# Sheet1.net
KiCad netlist of a schematic drawn in Altium Designer
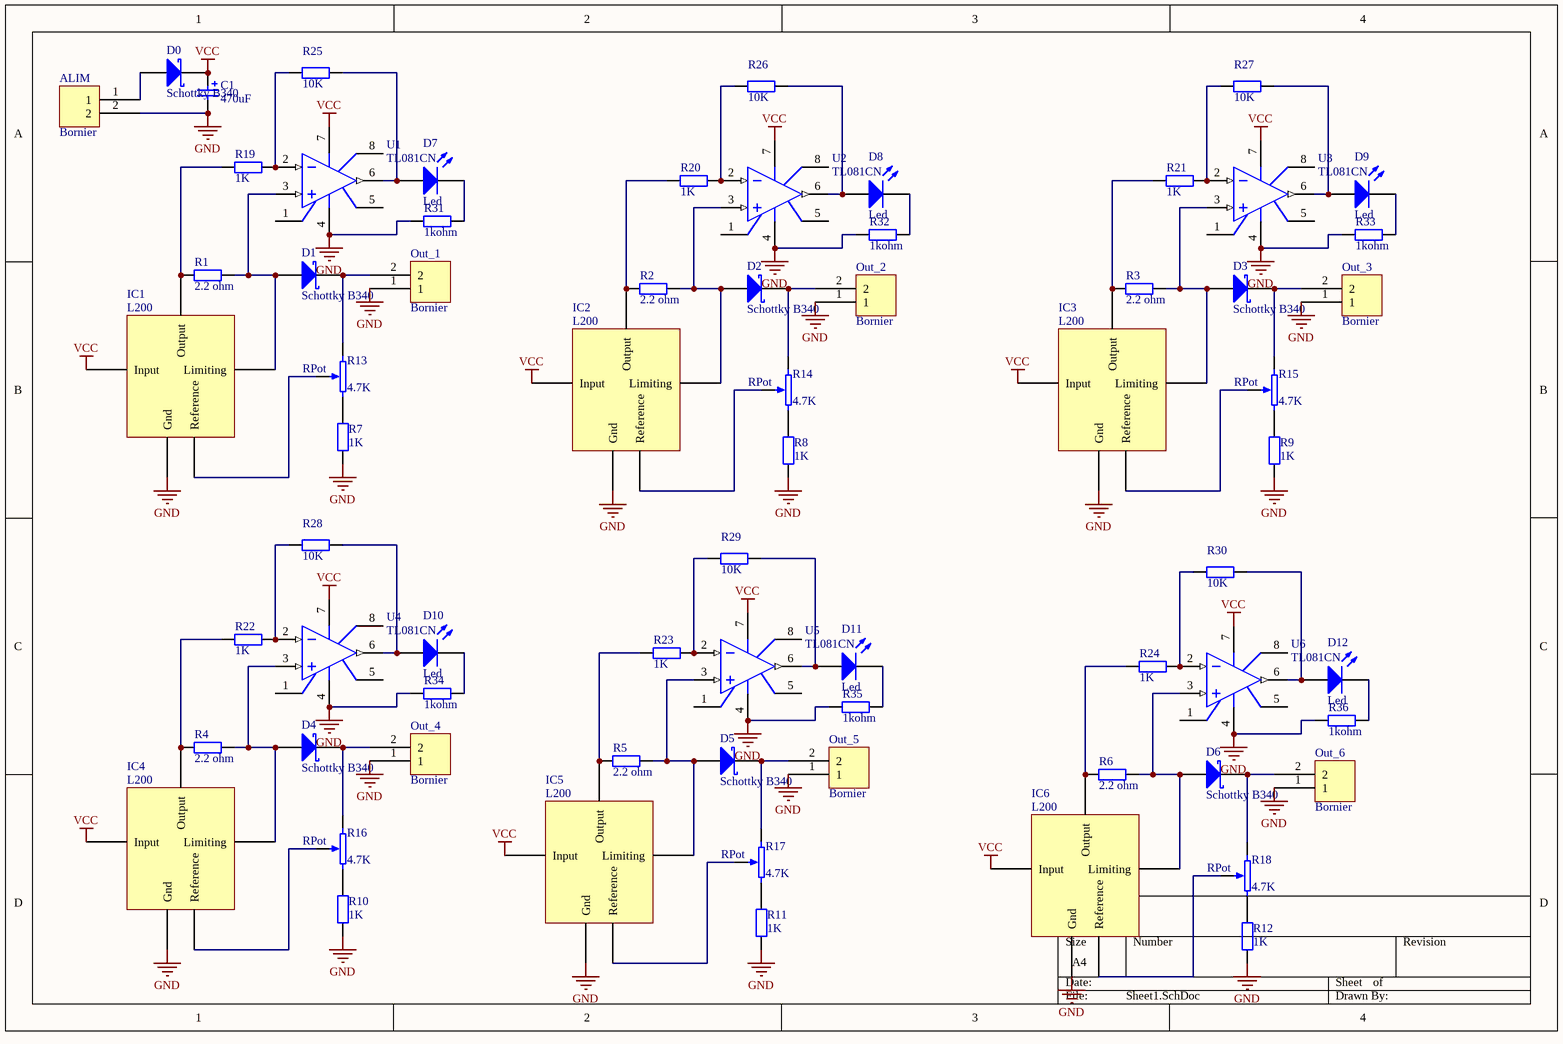
[diagram p0: Sheet1.SchDoc]

(export (version "E")
  (design (tool "Eeschema 10.0.6"))
  (components
    (comp (ref "ALIM") (value "Bornier") (footprint "Bornier") (libsource (lib "") (part "Bornier2_1")))
    (comp (ref "C1")
      (value "470uF")
      (footprint "Capa_pol1")
      (libsource (lib "lib_Robotronik") (part "Capa Pol"))
    )
    (comp (ref "D0")
      (value "Schottky B340")
      (footprint "SMC")
      (libsource (lib "lib_Robotronik") (part "Schottky B340"))
    )
    (comp (ref "D1")
      (value "Schottky B340")
      (footprint "SMC")
      (libsource (lib "lib_Robotronik") (part "Schottky B340"))
    )
    (comp (ref "D2")
      (value "Schottky B340")
      (footprint "SMC")
      (libsource (lib "lib_Robotronik") (part "Schottky B340"))
    )
    (comp (ref "D3")
      (value "Schottky B340")
      (footprint "SMC")
      (libsource (lib "lib_Robotronik") (part "Schottky B340"))
    )
    (comp (ref "D4")
      (value "Schottky B340")
      (footprint "SMC")
      (libsource (lib "lib_Robotronik") (part "Schottky B340"))
    )
    (comp (ref "D5")
      (value "Schottky B340")
      (footprint "SMC")
      (libsource (lib "lib_Robotronik") (part "Schottky B340"))
    )
    (comp (ref "D6")
      (value "Schottky B340")
      (footprint "SMC")
      (libsource (lib "lib_Robotronik") (part "Schottky B340"))
    )
    (comp (ref "D7")
      (value "Led")
      (footprint "LED")
      (description "LED")
      (fields (field (name "PUBLISHER") "Altium Limited"))
      (libsource (lib "LIBRAIRIE_INTEGREE_PHELMA1") (part "Led"))
    )
    (comp (ref "D8")
      (value "Led")
      (footprint "LED")
      (description "LED")
      (fields (field (name "PUBLISHER") "Altium Limited"))
      (libsource (lib "LIBRAIRIE_INTEGREE_PHELMA1") (part "Led"))
    )
    (comp (ref "D9")
      (value "Led")
      (footprint "LED")
      (description "LED")
      (fields (field (name "PUBLISHER") "Altium Limited"))
      (libsource (lib "LIBRAIRIE_INTEGREE_PHELMA1") (part "Led"))
    )
    (comp (ref "D10")
      (value "Led")
      (footprint "LED")
      (description "LED")
      (fields (field (name "PUBLISHER") "Altium Limited"))
      (libsource (lib "LIBRAIRIE_INTEGREE_PHELMA1") (part "Led"))
    )
    (comp (ref "D11")
      (value "Led")
      (footprint "LED")
      (description "LED")
      (fields (field (name "PUBLISHER") "Altium Limited"))
      (libsource (lib "LIBRAIRIE_INTEGREE_PHELMA1") (part "Led"))
    )
    (comp (ref "D12")
      (value "Led")
      (footprint "LED")
      (description "LED")
      (fields (field (name "PUBLISHER") "Altium Limited"))
      (libsource (lib "LIBRAIRIE_INTEGREE_PHELMA1") (part "Led"))
    )
    (comp (ref "IC1") (value "L200") (footprint "Pentawatt") (libsource (lib "lib_Robotronik") (part "L200")))
    (comp (ref "IC2") (value "L200") (footprint "Pentawatt") (libsource (lib "lib_Robotronik") (part "L200")))
    (comp (ref "IC3") (value "L200") (footprint "Pentawatt") (libsource (lib "lib_Robotronik") (part "L200")))
    (comp (ref "IC4") (value "L200") (footprint "Pentawatt") (libsource (lib "lib_Robotronik") (part "L200")))
    (comp (ref "IC5") (value "L200") (footprint "Pentawatt") (libsource (lib "lib_Robotronik") (part "L200")))
    (comp (ref "IC6") (value "L200") (footprint "Pentawatt") (libsource (lib "lib_Robotronik") (part "L200")))
    (comp (ref "Out_1")
      (value "Bornier")
      (footprint "Bornier")
      (libsource (lib "lib_Robotronik") (part "Bornier2"))
    )
    (comp (ref "Out_2")
      (value "Bornier")
      (footprint "Bornier")
      (libsource (lib "lib_Robotronik") (part "Bornier2"))
    )
    (comp (ref "Out_3")
      (value "Bornier")
      (footprint "Bornier")
      (libsource (lib "lib_Robotronik") (part "Bornier2"))
    )
    (comp (ref "Out_4")
      (value "Bornier")
      (footprint "Bornier")
      (libsource (lib "lib_Robotronik") (part "Bornier2"))
    )
    (comp (ref "Out_5")
      (value "Bornier")
      (footprint "Bornier")
      (libsource (lib "lib_Robotronik") (part "Bornier2"))
    )
    (comp (ref "Out_6")
      (value "Bornier")
      (footprint "Bornier")
      (libsource (lib "lib_Robotronik") (part "Bornier2"))
    )
    (comp (ref "R1")
      (value "2.2 ohm")
      (footprint "traversant 1/4W")
      (libsource (lib "") (part "Resistance_2"))
    )
    (comp (ref "R2")
      (value "2.2 ohm")
      (footprint "traversant 1/4W")
      (libsource (lib "") (part "Resistance_2"))
    )
    (comp (ref "R3")
      (value "2.2 ohm")
      (footprint "traversant 1/4W")
      (libsource (lib "") (part "Resistance_2"))
    )
    (comp (ref "R4")
      (value "2.2 ohm")
      (footprint "traversant 1/4W")
      (libsource (lib "") (part "Resistance_2"))
    )
    (comp (ref "R5")
      (value "2.2 ohm")
      (footprint "traversant 1/4W")
      (libsource (lib "") (part "Resistance_2"))
    )
    (comp (ref "R6")
      (value "2.2 ohm")
      (footprint "traversant 1/4W")
      (libsource (lib "") (part "Resistance_2"))
    )
    (comp (ref "R7") (value "1K") (footprint "traversant 1/4W") (libsource (lib "") (part "Resistance_1")))
    (comp (ref "R8") (value "1K") (footprint "traversant 1/4W") (libsource (lib "") (part "Resistance_1")))
    (comp (ref "R9") (value "1K") (footprint "traversant 1/4W") (libsource (lib "") (part "Resistance_1")))
    (comp (ref "R10") (value "1K") (footprint "traversant 1/4W") (libsource (lib "") (part "Resistance_1")))
    (comp (ref "R11") (value "1K") (footprint "traversant 1/4W") (libsource (lib "") (part "Resistance_1")))
    (comp (ref "R12") (value "1K") (footprint "traversant 1/4W") (libsource (lib "") (part "Resistance_1")))
    (comp (ref "R13")
      (value "RPot")
      (footprint "AJUSTABLE")
      (description "Potentiometer")
      (fields (field (name "ALTIUM_VALUE") "4.7K") (field (name "PUBLISHER") "Altium Limited"))
      (libsource (lib "LIBRAIRIE_INTEGREE_PHELMA1") (part "RPot"))
    )
    (comp (ref "R14")
      (value "RPot")
      (footprint "AJUSTABLE")
      (description "Potentiometer")
      (fields (field (name "ALTIUM_VALUE") "4.7K") (field (name "PUBLISHER") "Altium Limited"))
      (libsource (lib "LIBRAIRIE_INTEGREE_PHELMA1") (part "RPot"))
    )
    (comp (ref "R15")
      (value "RPot")
      (footprint "AJUSTABLE")
      (description "Potentiometer")
      (fields (field (name "ALTIUM_VALUE") "4.7K") (field (name "PUBLISHER") "Altium Limited"))
      (libsource (lib "LIBRAIRIE_INTEGREE_PHELMA1") (part "RPot"))
    )
    (comp (ref "R16")
      (value "RPot")
      (footprint "AJUSTABLE")
      (description "Potentiometer")
      (fields (field (name "ALTIUM_VALUE") "4.7K") (field (name "PUBLISHER") "Altium Limited"))
      (libsource (lib "LIBRAIRIE_INTEGREE_PHELMA1") (part "RPot"))
    )
    (comp (ref "R17")
      (value "RPot")
      (footprint "AJUSTABLE")
      (description "Potentiometer")
      (fields (field (name "ALTIUM_VALUE") "4.7K") (field (name "PUBLISHER") "Altium Limited"))
      (libsource (lib "LIBRAIRIE_INTEGREE_PHELMA1") (part "RPot"))
    )
    (comp (ref "R18")
      (value "RPot")
      (footprint "AJUSTABLE")
      (description "Potentiometer")
      (fields (field (name "ALTIUM_VALUE") "4.7K") (field (name "PUBLISHER") "Altium Limited"))
      (libsource (lib "LIBRAIRIE_INTEGREE_PHELMA1") (part "RPot"))
    )
    (comp (ref "R19") (value "1K") (footprint "traversant 1/4W") (libsource (lib "") (part "Resistance_2")))
    (comp (ref "R20") (value "1K") (footprint "traversant 1/4W") (libsource (lib "") (part "Resistance_2")))
    (comp (ref "R21") (value "1K") (footprint "traversant 1/4W") (libsource (lib "") (part "Resistance_2")))
    (comp (ref "R22") (value "1K") (footprint "traversant 1/4W") (libsource (lib "") (part "Resistance_2")))
    (comp (ref "R23") (value "1K") (footprint "traversant 1/4W") (libsource (lib "") (part "Resistance_2")))
    (comp (ref "R24") (value "1K") (footprint "traversant 1/4W") (libsource (lib "") (part "Resistance_2")))
    (comp (ref "R25") (value "10K") (footprint "traversant 1/4W") (libsource (lib "") (part "Resistance_2")))
    (comp (ref "R26") (value "10K") (footprint "traversant 1/4W") (libsource (lib "") (part "Resistance_2")))
    (comp (ref "R27") (value "10K") (footprint "traversant 1/4W") (libsource (lib "") (part "Resistance_2")))
    (comp (ref "R28") (value "10K") (footprint "traversant 1/4W") (libsource (lib "") (part "Resistance_2")))
    (comp (ref "R29") (value "10K") (footprint "traversant 1/4W") (libsource (lib "") (part "Resistance_2")))
    (comp (ref "R30") (value "10K") (footprint "traversant 1/4W") (libsource (lib "") (part "Resistance_2")))
    (comp (ref "R31")
      (value "1kohm")
      (footprint "traversant 1/4W")
      (libsource (lib "lib_Robotronik") (part "Resistance"))
    )
    (comp (ref "R32")
      (value "1kohm")
      (footprint "traversant 1/4W")
      (libsource (lib "lib_Robotronik") (part "Resistance"))
    )
    (comp (ref "R33")
      (value "1kohm")
      (footprint "traversant 1/4W")
      (libsource (lib "lib_Robotronik") (part "Resistance"))
    )
    (comp (ref "R34")
      (value "1kohm")
      (footprint "traversant 1/4W")
      (libsource (lib "lib_Robotronik") (part "Resistance"))
    )
    (comp (ref "R35")
      (value "1kohm")
      (footprint "traversant 1/4W")
      (libsource (lib "lib_Robotronik") (part "Resistance"))
    )
    (comp (ref "R36")
      (value "1kohm")
      (footprint "traversant 1/4W")
      (libsource (lib "lib_Robotronik") (part "Resistance"))
    )
    (comp (ref "U1")
      (value "TL081CN")
      (footprint "DIP8")
      (description "General-Purpose J-FET Single Operational Amplifier")
      (fields (field (name "PUBLISHER") "Altium Limited"))
      (libsource (lib "LIBRAIRIE_INTEGREE_PHELMA1") (part "TL081CN"))
    )
    (comp (ref "U2")
      (value "TL081CN")
      (footprint "DIP8")
      (description "General-Purpose J-FET Single Operational Amplifier")
      (fields (field (name "PUBLISHER") "Altium Limited"))
      (libsource (lib "LIBRAIRIE_INTEGREE_PHELMA1") (part "TL081CN"))
    )
    (comp (ref "U3")
      (value "TL081CN")
      (footprint "DIP8")
      (description "General-Purpose J-FET Single Operational Amplifier")
      (fields (field (name "PUBLISHER") "Altium Limited"))
      (libsource (lib "LIBRAIRIE_INTEGREE_PHELMA1") (part "TL081CN"))
    )
    (comp (ref "U4")
      (value "TL081CN")
      (footprint "DIP8")
      (description "General-Purpose J-FET Single Operational Amplifier")
      (fields (field (name "PUBLISHER") "Altium Limited"))
      (libsource (lib "LIBRAIRIE_INTEGREE_PHELMA1") (part "TL081CN"))
    )
    (comp (ref "U5")
      (value "TL081CN")
      (footprint "DIP8")
      (description "General-Purpose J-FET Single Operational Amplifier")
      (fields (field (name "PUBLISHER") "Altium Limited"))
      (libsource (lib "LIBRAIRIE_INTEGREE_PHELMA1") (part "TL081CN"))
    )
    (comp (ref "U6")
      (value "TL081CN")
      (footprint "DIP8")
      (description "General-Purpose J-FET Single Operational Amplifier")
      (fields (field (name "PUBLISHER") "Altium Limited"))
      (libsource (lib "LIBRAIRIE_INTEGREE_PHELMA1") (part "TL081CN"))
    )
  )
  (nets
    (net (code "1") (name "GND") (class "Default")
      (node (ref "ALIM") (pin "2") (pinfunction "2_2") (pintype "passive"))
      (node (ref "C1") (pin "2") (pinfunction "2_2") (pintype "passive"))
      (node (ref "IC1") (pin "3") (pinfunction "Gnd_3") (pintype "passive"))
      (node (ref "IC2") (pin "3") (pinfunction "Gnd_3") (pintype "passive"))
      (node (ref "IC3") (pin "3") (pinfunction "Gnd_3") (pintype "passive"))
      (node (ref "IC4") (pin "3") (pinfunction "Gnd_3") (pintype "passive"))
      (node (ref "IC5") (pin "3") (pinfunction "Gnd_3") (pintype "passive"))
      (node (ref "IC6") (pin "3") (pinfunction "Gnd_3") (pintype "passive"))
      (node (ref "Out_1") (pin "1") (pinfunction "1_1") (pintype "passive"))
      (node (ref "Out_2") (pin "1") (pinfunction "1_1") (pintype "passive"))
      (node (ref "Out_3") (pin "1") (pinfunction "1_1") (pintype "passive"))
      (node (ref "Out_4") (pin "1") (pinfunction "1_1") (pintype "passive"))
      (node (ref "Out_5") (pin "1") (pinfunction "1_1") (pintype "passive"))
      (node (ref "Out_6") (pin "1") (pinfunction "1_1") (pintype "passive"))
      (node (ref "R10") (pin "1") (pinfunction "1_1") (pintype "passive"))
      (node (ref "R11") (pin "1") (pinfunction "1_1") (pintype "passive"))
      (node (ref "R12") (pin "1") (pinfunction "1_1") (pintype "passive"))
      (node (ref "R31") (pin "1") (pinfunction "1_1") (pintype "passive"))
      (node (ref "R32") (pin "1") (pinfunction "1_1") (pintype "passive"))
      (node (ref "R33") (pin "1") (pinfunction "1_1") (pintype "passive"))
      (node (ref "R34") (pin "1") (pinfunction "1_1") (pintype "passive"))
      (node (ref "R35") (pin "1") (pinfunction "1_1") (pintype "passive"))
      (node (ref "R36") (pin "1") (pinfunction "1_1") (pintype "passive"))
      (node (ref "R7") (pin "1") (pinfunction "1_1") (pintype "passive"))
      (node (ref "R8") (pin "1") (pinfunction "1_1") (pintype "passive"))
      (node (ref "R9") (pin "1") (pinfunction "1_1") (pintype "passive"))
      (node (ref "U1") (pin "4") (pinfunction "V-_4") (pintype "power_in"))
      (node (ref "U2") (pin "4") (pinfunction "V-_4") (pintype "power_in"))
      (node (ref "U3") (pin "4") (pinfunction "V-_4") (pintype "power_in"))
      (node (ref "U4") (pin "4") (pinfunction "V-_4") (pintype "power_in"))
      (node (ref "U5") (pin "4") (pinfunction "V-_4") (pintype "power_in"))
      (node (ref "U6") (pin "4") (pinfunction "V-_4") (pintype "power_in"))
    )
    (net (code "2") (name "Net-(D0-A)") (class "Default")
      (node (ref "ALIM") (pin "1") (pinfunction "1_1") (pintype "passive"))
      (node (ref "D0") (pin "1") (pinfunction "A_1") (pintype "passive"))
    )
    (net (code "3") (name "Net-(D1-A)") (class "Default")
      (node (ref "D1") (pin "1") (pinfunction "A_1") (pintype "passive"))
      (node (ref "IC1") (pin "2") (pinfunction "Limiting_2") (pintype "passive"))
      (node (ref "R1") (pin "1") (pinfunction "1_1") (pintype "passive"))
      (node (ref "U1") (pin "3") (pinfunction "IN+_3") (pintype "input"))
    )
    (net (code "4") (name "Net-(D1-K)") (class "Default")
      (node (ref "D1") (pin "2") (pinfunction "K_2") (pintype "passive"))
      (node (ref "Out_1") (pin "2") (pinfunction "2_2") (pintype "passive"))
      (node (ref "R13") (pin "3") (pinfunction "TOP_3") (pintype "passive"))
    )
    (net (code "5") (name "Net-(D2-A)") (class "Default")
      (node (ref "D2") (pin "1") (pinfunction "A_1") (pintype "passive"))
      (node (ref "IC2") (pin "2") (pinfunction "Limiting_2") (pintype "passive"))
      (node (ref "R2") (pin "1") (pinfunction "1_1") (pintype "passive"))
      (node (ref "U2") (pin "3") (pinfunction "IN+_3") (pintype "input"))
    )
    (net (code "6") (name "Net-(D2-K)") (class "Default")
      (node (ref "D2") (pin "2") (pinfunction "K_2") (pintype "passive"))
      (node (ref "Out_2") (pin "2") (pinfunction "2_2") (pintype "passive"))
      (node (ref "R14") (pin "3") (pinfunction "TOP_3") (pintype "passive"))
    )
    (net (code "7") (name "Net-(D3-A)") (class "Default")
      (node (ref "D3") (pin "1") (pinfunction "A_1") (pintype "passive"))
      (node (ref "IC3") (pin "2") (pinfunction "Limiting_2") (pintype "passive"))
      (node (ref "R3") (pin "1") (pinfunction "1_1") (pintype "passive"))
      (node (ref "U3") (pin "3") (pinfunction "IN+_3") (pintype "input"))
    )
    (net (code "8") (name "Net-(D3-K)") (class "Default")
      (node (ref "D3") (pin "2") (pinfunction "K_2") (pintype "passive"))
      (node (ref "Out_3") (pin "2") (pinfunction "2_2") (pintype "passive"))
      (node (ref "R15") (pin "3") (pinfunction "TOP_3") (pintype "passive"))
    )
    (net (code "9") (name "Net-(D4-A)") (class "Default")
      (node (ref "D4") (pin "1") (pinfunction "A_1") (pintype "passive"))
      (node (ref "IC4") (pin "2") (pinfunction "Limiting_2") (pintype "passive"))
      (node (ref "R4") (pin "1") (pinfunction "1_1") (pintype "passive"))
      (node (ref "U4") (pin "3") (pinfunction "IN+_3") (pintype "input"))
    )
    (net (code "10") (name "Net-(D4-K)") (class "Default")
      (node (ref "D4") (pin "2") (pinfunction "K_2") (pintype "passive"))
      (node (ref "Out_4") (pin "2") (pinfunction "2_2") (pintype "passive"))
      (node (ref "R16") (pin "3") (pinfunction "TOP_3") (pintype "passive"))
    )
    (net (code "11") (name "Net-(D5-A)") (class "Default")
      (node (ref "D5") (pin "1") (pinfunction "A_1") (pintype "passive"))
      (node (ref "IC5") (pin "2") (pinfunction "Limiting_2") (pintype "passive"))
      (node (ref "R5") (pin "1") (pinfunction "1_1") (pintype "passive"))
      (node (ref "U5") (pin "3") (pinfunction "IN+_3") (pintype "input"))
    )
    (net (code "12") (name "Net-(D5-K)") (class "Default")
      (node (ref "D5") (pin "2") (pinfunction "K_2") (pintype "passive"))
      (node (ref "Out_5") (pin "2") (pinfunction "2_2") (pintype "passive"))
      (node (ref "R17") (pin "3") (pinfunction "TOP_3") (pintype "passive"))
    )
    (net (code "13") (name "Net-(D6-A)") (class "Default")
      (node (ref "D6") (pin "1") (pinfunction "A_1") (pintype "passive"))
      (node (ref "IC6") (pin "2") (pinfunction "Limiting_2") (pintype "passive"))
      (node (ref "R6") (pin "1") (pinfunction "1_1") (pintype "passive"))
      (node (ref "U6") (pin "3") (pinfunction "IN+_3") (pintype "input"))
    )
    (net (code "14") (name "Net-(D6-K)") (class "Default")
      (node (ref "D6") (pin "2") (pinfunction "K_2") (pintype "passive"))
      (node (ref "Out_6") (pin "2") (pinfunction "2_2") (pintype "passive"))
      (node (ref "R18") (pin "3") (pinfunction "TOP_3") (pintype "passive"))
    )
    (net (code "15") (name "Net-(D7-A)") (class "Default")
      (node (ref "D7") (pin "1") (pinfunction "A_1") (pintype "passive"))
      (node (ref "R25") (pin "1") (pinfunction "1_1") (pintype "passive"))
      (node (ref "U1") (pin "6") (pinfunction "OUT_6") (pintype "output"))
    )
    (net (code "16") (name "Net-(D7-K)") (class "Default")
      (node (ref "D7") (pin "2") (pinfunction "K_2") (pintype "passive"))
      (node (ref "R31") (pin "2") (pinfunction "2_2") (pintype "passive"))
    )
    (net (code "17") (name "Net-(D8-A)") (class "Default")
      (node (ref "D8") (pin "1") (pinfunction "A_1") (pintype "passive"))
      (node (ref "R26") (pin "1") (pinfunction "1_1") (pintype "passive"))
      (node (ref "U2") (pin "6") (pinfunction "OUT_6") (pintype "output"))
    )
    (net (code "18") (name "Net-(D8-K)") (class "Default")
      (node (ref "D8") (pin "2") (pinfunction "K_2") (pintype "passive"))
      (node (ref "R32") (pin "2") (pinfunction "2_2") (pintype "passive"))
    )
    (net (code "19") (name "Net-(D9-A)") (class "Default")
      (node (ref "D9") (pin "1") (pinfunction "A_1") (pintype "passive"))
      (node (ref "R27") (pin "1") (pinfunction "1_1") (pintype "passive"))
      (node (ref "U3") (pin "6") (pinfunction "OUT_6") (pintype "output"))
    )
    (net (code "20") (name "Net-(D9-K)") (class "Default")
      (node (ref "D9") (pin "2") (pinfunction "K_2") (pintype "passive"))
      (node (ref "R33") (pin "2") (pinfunction "2_2") (pintype "passive"))
    )
    (net (code "21") (name "Net-(D10-A)") (class "Default")
      (node (ref "D10") (pin "1") (pinfunction "A_1") (pintype "passive"))
      (node (ref "R28") (pin "1") (pinfunction "1_1") (pintype "passive"))
      (node (ref "U4") (pin "6") (pinfunction "OUT_6") (pintype "output"))
    )
    (net (code "22") (name "Net-(D10-K)") (class "Default")
      (node (ref "D10") (pin "2") (pinfunction "K_2") (pintype "passive"))
      (node (ref "R34") (pin "2") (pinfunction "2_2") (pintype "passive"))
    )
    (net (code "23") (name "Net-(D11-A)") (class "Default")
      (node (ref "D11") (pin "1") (pinfunction "A_1") (pintype "passive"))
      (node (ref "R29") (pin "1") (pinfunction "1_1") (pintype "passive"))
      (node (ref "U5") (pin "6") (pinfunction "OUT_6") (pintype "output"))
    )
    (net (code "24") (name "Net-(D11-K)") (class "Default")
      (node (ref "D11") (pin "2") (pinfunction "K_2") (pintype "passive"))
      (node (ref "R35") (pin "2") (pinfunction "2_2") (pintype "passive"))
    )
    (net (code "25") (name "Net-(D12-A)") (class "Default")
      (node (ref "D12") (pin "1") (pinfunction "A_1") (pintype "passive"))
      (node (ref "R30") (pin "1") (pinfunction "1_1") (pintype "passive"))
      (node (ref "U6") (pin "6") (pinfunction "OUT_6") (pintype "output"))
    )
    (net (code "26") (name "Net-(D12-K)") (class "Default")
      (node (ref "D12") (pin "2") (pinfunction "K_2") (pintype "passive"))
      (node (ref "R36") (pin "2") (pinfunction "2_2") (pintype "passive"))
    )
    (net (code "27") (name "Net-(IC1-Output)") (class "Default")
      (node (ref "IC1") (pin "5") (pinfunction "Output_5") (pintype "passive"))
      (node (ref "R1") (pin "2") (pinfunction "2_2") (pintype "passive"))
      (node (ref "R19") (pin "2") (pinfunction "2_2") (pintype "passive"))
    )
    (net (code "28") (name "Net-(IC1-Reference)") (class "Default")
      (node (ref "IC1") (pin "4") (pinfunction "Reference_4") (pintype "passive"))
      (node (ref "R13") (pin "2") (pinfunction "TAP_2") (pintype "passive"))
    )
    (net (code "29") (name "Net-(IC2-Output)") (class "Default")
      (node (ref "IC2") (pin "5") (pinfunction "Output_5") (pintype "passive"))
      (node (ref "R2") (pin "2") (pinfunction "2_2") (pintype "passive"))
      (node (ref "R20") (pin "2") (pinfunction "2_2") (pintype "passive"))
    )
    (net (code "30") (name "Net-(IC2-Reference)") (class "Default")
      (node (ref "IC2") (pin "4") (pinfunction "Reference_4") (pintype "passive"))
      (node (ref "R14") (pin "2") (pinfunction "TAP_2") (pintype "passive"))
    )
    (net (code "31") (name "Net-(IC3-Output)") (class "Default")
      (node (ref "IC3") (pin "5") (pinfunction "Output_5") (pintype "passive"))
      (node (ref "R21") (pin "2") (pinfunction "2_2") (pintype "passive"))
      (node (ref "R3") (pin "2") (pinfunction "2_2") (pintype "passive"))
    )
    (net (code "32") (name "Net-(IC3-Reference)") (class "Default")
      (node (ref "IC3") (pin "4") (pinfunction "Reference_4") (pintype "passive"))
      (node (ref "R15") (pin "2") (pinfunction "TAP_2") (pintype "passive"))
    )
    (net (code "33") (name "Net-(IC4-Output)") (class "Default")
      (node (ref "IC4") (pin "5") (pinfunction "Output_5") (pintype "passive"))
      (node (ref "R22") (pin "2") (pinfunction "2_2") (pintype "passive"))
      (node (ref "R4") (pin "2") (pinfunction "2_2") (pintype "passive"))
    )
    (net (code "34") (name "Net-(IC4-Reference)") (class "Default")
      (node (ref "IC4") (pin "4") (pinfunction "Reference_4") (pintype "passive"))
      (node (ref "R16") (pin "2") (pinfunction "TAP_2") (pintype "passive"))
    )
    (net (code "35") (name "Net-(IC5-Output)") (class "Default")
      (node (ref "IC5") (pin "5") (pinfunction "Output_5") (pintype "passive"))
      (node (ref "R23") (pin "2") (pinfunction "2_2") (pintype "passive"))
      (node (ref "R5") (pin "2") (pinfunction "2_2") (pintype "passive"))
    )
    (net (code "36") (name "Net-(IC5-Reference)") (class "Default")
      (node (ref "IC5") (pin "4") (pinfunction "Reference_4") (pintype "passive"))
      (node (ref "R17") (pin "2") (pinfunction "TAP_2") (pintype "passive"))
    )
    (net (code "37") (name "Net-(IC6-Output)") (class "Default")
      (node (ref "IC6") (pin "5") (pinfunction "Output_5") (pintype "passive"))
      (node (ref "R24") (pin "2") (pinfunction "2_2") (pintype "passive"))
      (node (ref "R6") (pin "2") (pinfunction "2_2") (pintype "passive"))
    )
    (net (code "38") (name "Net-(IC6-Reference)") (class "Default")
      (node (ref "IC6") (pin "4") (pinfunction "Reference_4") (pintype "passive"))
      (node (ref "R18") (pin "2") (pinfunction "TAP_2") (pintype "passive"))
    )
    (net (code "39") (name "Net-(R13-BOT)") (class "Default")
      (node (ref "R13") (pin "1") (pinfunction "BOT_1") (pintype "passive"))
      (node (ref "R7") (pin "2") (pinfunction "2_2") (pintype "passive"))
    )
    (net (code "40") (name "Net-(R14-BOT)") (class "Default")
      (node (ref "R14") (pin "1") (pinfunction "BOT_1") (pintype "passive"))
      (node (ref "R8") (pin "2") (pinfunction "2_2") (pintype "passive"))
    )
    (net (code "41") (name "Net-(R15-BOT)") (class "Default")
      (node (ref "R15") (pin "1") (pinfunction "BOT_1") (pintype "passive"))
      (node (ref "R9") (pin "2") (pinfunction "2_2") (pintype "passive"))
    )
    (net (code "42") (name "Net-(R16-BOT)") (class "Default")
      (node (ref "R10") (pin "2") (pinfunction "2_2") (pintype "passive"))
      (node (ref "R16") (pin "1") (pinfunction "BOT_1") (pintype "passive"))
    )
    (net (code "43") (name "Net-(R17-BOT)") (class "Default")
      (node (ref "R11") (pin "2") (pinfunction "2_2") (pintype "passive"))
      (node (ref "R17") (pin "1") (pinfunction "BOT_1") (pintype "passive"))
    )
    (net (code "44") (name "Net-(R18-BOT)") (class "Default")
      (node (ref "R12") (pin "2") (pinfunction "2_2") (pintype "passive"))
      (node (ref "R18") (pin "1") (pinfunction "BOT_1") (pintype "passive"))
    )
    (net (code "45") (name "Net-(U1-IN-)") (class "Default")
      (node (ref "R19") (pin "1") (pinfunction "1_1") (pintype "passive"))
      (node (ref "R25") (pin "2") (pinfunction "2_2") (pintype "passive"))
      (node (ref "U1") (pin "2") (pinfunction "IN-_2") (pintype "input"))
    )
    (net (code "46") (name "Net-(U2-IN-)") (class "Default")
      (node (ref "R20") (pin "1") (pinfunction "1_1") (pintype "passive"))
      (node (ref "R26") (pin "2") (pinfunction "2_2") (pintype "passive"))
      (node (ref "U2") (pin "2") (pinfunction "IN-_2") (pintype "input"))
    )
    (net (code "47") (name "Net-(U3-IN-)") (class "Default")
      (node (ref "R21") (pin "1") (pinfunction "1_1") (pintype "passive"))
      (node (ref "R27") (pin "2") (pinfunction "2_2") (pintype "passive"))
      (node (ref "U3") (pin "2") (pinfunction "IN-_2") (pintype "input"))
    )
    (net (code "48") (name "Net-(U4-IN-)") (class "Default")
      (node (ref "R22") (pin "1") (pinfunction "1_1") (pintype "passive"))
      (node (ref "R28") (pin "2") (pinfunction "2_2") (pintype "passive"))
      (node (ref "U4") (pin "2") (pinfunction "IN-_2") (pintype "input"))
    )
    (net (code "49") (name "Net-(U5-IN-)") (class "Default")
      (node (ref "R23") (pin "1") (pinfunction "1_1") (pintype "passive"))
      (node (ref "R29") (pin "2") (pinfunction "2_2") (pintype "passive"))
      (node (ref "U5") (pin "2") (pinfunction "IN-_2") (pintype "input"))
    )
    (net (code "50") (name "Net-(U6-IN-)") (class "Default")
      (node (ref "R24") (pin "1") (pinfunction "1_1") (pintype "passive"))
      (node (ref "R30") (pin "2") (pinfunction "2_2") (pintype "passive"))
      (node (ref "U6") (pin "2") (pinfunction "IN-_2") (pintype "input"))
    )
    (net (code "51") (name "VCC") (class "Default")
      (node (ref "C1") (pin "1") (pinfunction "1_1") (pintype "passive"))
      (node (ref "D0") (pin "2") (pinfunction "K_2") (pintype "passive"))
      (node (ref "IC1") (pin "1") (pinfunction "Input_1") (pintype "passive"))
      (node (ref "IC2") (pin "1") (pinfunction "Input_1") (pintype "passive"))
      (node (ref "IC3") (pin "1") (pinfunction "Input_1") (pintype "passive"))
      (node (ref "IC4") (pin "1") (pinfunction "Input_1") (pintype "passive"))
      (node (ref "IC5") (pin "1") (pinfunction "Input_1") (pintype "passive"))
      (node (ref "IC6") (pin "1") (pinfunction "Input_1") (pintype "passive"))
      (node (ref "U1") (pin "7") (pinfunction "V+_7") (pintype "power_in"))
      (node (ref "U2") (pin "7") (pinfunction "V+_7") (pintype "power_in"))
      (node (ref "U3") (pin "7") (pinfunction "V+_7") (pintype "power_in"))
      (node (ref "U4") (pin "7") (pinfunction "V+_7") (pintype "power_in"))
      (node (ref "U5") (pin "7") (pinfunction "V+_7") (pintype "power_in"))
      (node (ref "U6") (pin "7") (pinfunction "V+_7") (pintype "power_in"))
    )
    (net (code "52") (name "unconnected-(U1-NC-Pad8)") (class "Default")
      (node (ref "U1") (pin "8") (pinfunction "NC_8") (pintype "passive"))
    )
    (net (code "53") (name "unconnected-(U1-OS_NULL-Pad1)") (class "Default")
      (node (ref "U1") (pin "1") (pinfunction "OS_NULL_1") (pintype "passive"))
    )
    (net (code "54") (name "unconnected-(U1-OS_NULL-Pad5)") (class "Default")
      (node (ref "U1") (pin "5") (pinfunction "OS_NULL_5") (pintype "passive"))
    )
    (net (code "55") (name "unconnected-(U2-NC-Pad8)") (class "Default")
      (node (ref "U2") (pin "8") (pinfunction "NC_8") (pintype "passive"))
    )
    (net (code "56") (name "unconnected-(U2-OS_NULL-Pad1)") (class "Default")
      (node (ref "U2") (pin "1") (pinfunction "OS_NULL_1") (pintype "passive"))
    )
    (net (code "57") (name "unconnected-(U2-OS_NULL-Pad5)") (class "Default")
      (node (ref "U2") (pin "5") (pinfunction "OS_NULL_5") (pintype "passive"))
    )
    (net (code "58") (name "unconnected-(U3-NC-Pad8)") (class "Default")
      (node (ref "U3") (pin "8") (pinfunction "NC_8") (pintype "passive"))
    )
    (net (code "59") (name "unconnected-(U3-OS_NULL-Pad1)") (class "Default")
      (node (ref "U3") (pin "1") (pinfunction "OS_NULL_1") (pintype "passive"))
    )
    (net (code "60") (name "unconnected-(U3-OS_NULL-Pad5)") (class "Default")
      (node (ref "U3") (pin "5") (pinfunction "OS_NULL_5") (pintype "passive"))
    )
    (net (code "61") (name "unconnected-(U4-NC-Pad8)") (class "Default")
      (node (ref "U4") (pin "8") (pinfunction "NC_8") (pintype "passive"))
    )
    (net (code "62") (name "unconnected-(U4-OS_NULL-Pad1)") (class "Default")
      (node (ref "U4") (pin "1") (pinfunction "OS_NULL_1") (pintype "passive"))
    )
    (net (code "63") (name "unconnected-(U4-OS_NULL-Pad5)") (class "Default")
      (node (ref "U4") (pin "5") (pinfunction "OS_NULL_5") (pintype "passive"))
    )
    (net (code "64") (name "unconnected-(U5-NC-Pad8)") (class "Default")
      (node (ref "U5") (pin "8") (pinfunction "NC_8") (pintype "passive"))
    )
    (net (code "65") (name "unconnected-(U5-OS_NULL-Pad1)") (class "Default")
      (node (ref "U5") (pin "1") (pinfunction "OS_NULL_1") (pintype "passive"))
    )
    (net (code "66") (name "unconnected-(U5-OS_NULL-Pad5)") (class "Default")
      (node (ref "U5") (pin "5") (pinfunction "OS_NULL_5") (pintype "passive"))
    )
    (net (code "67") (name "unconnected-(U6-NC-Pad8)") (class "Default")
      (node (ref "U6") (pin "8") (pinfunction "NC_8") (pintype "passive"))
    )
    (net (code "68") (name "unconnected-(U6-OS_NULL-Pad1)") (class "Default")
      (node (ref "U6") (pin "1") (pinfunction "OS_NULL_1") (pintype "passive"))
    )
    (net (code "69") (name "unconnected-(U6-OS_NULL-Pad5)") (class "Default")
      (node (ref "U6") (pin "5") (pinfunction "OS_NULL_5") (pintype "passive"))
    )
  )
)
